# LED_Chaser.net
KiCad netlist of a schematic drawn in Altium Designer
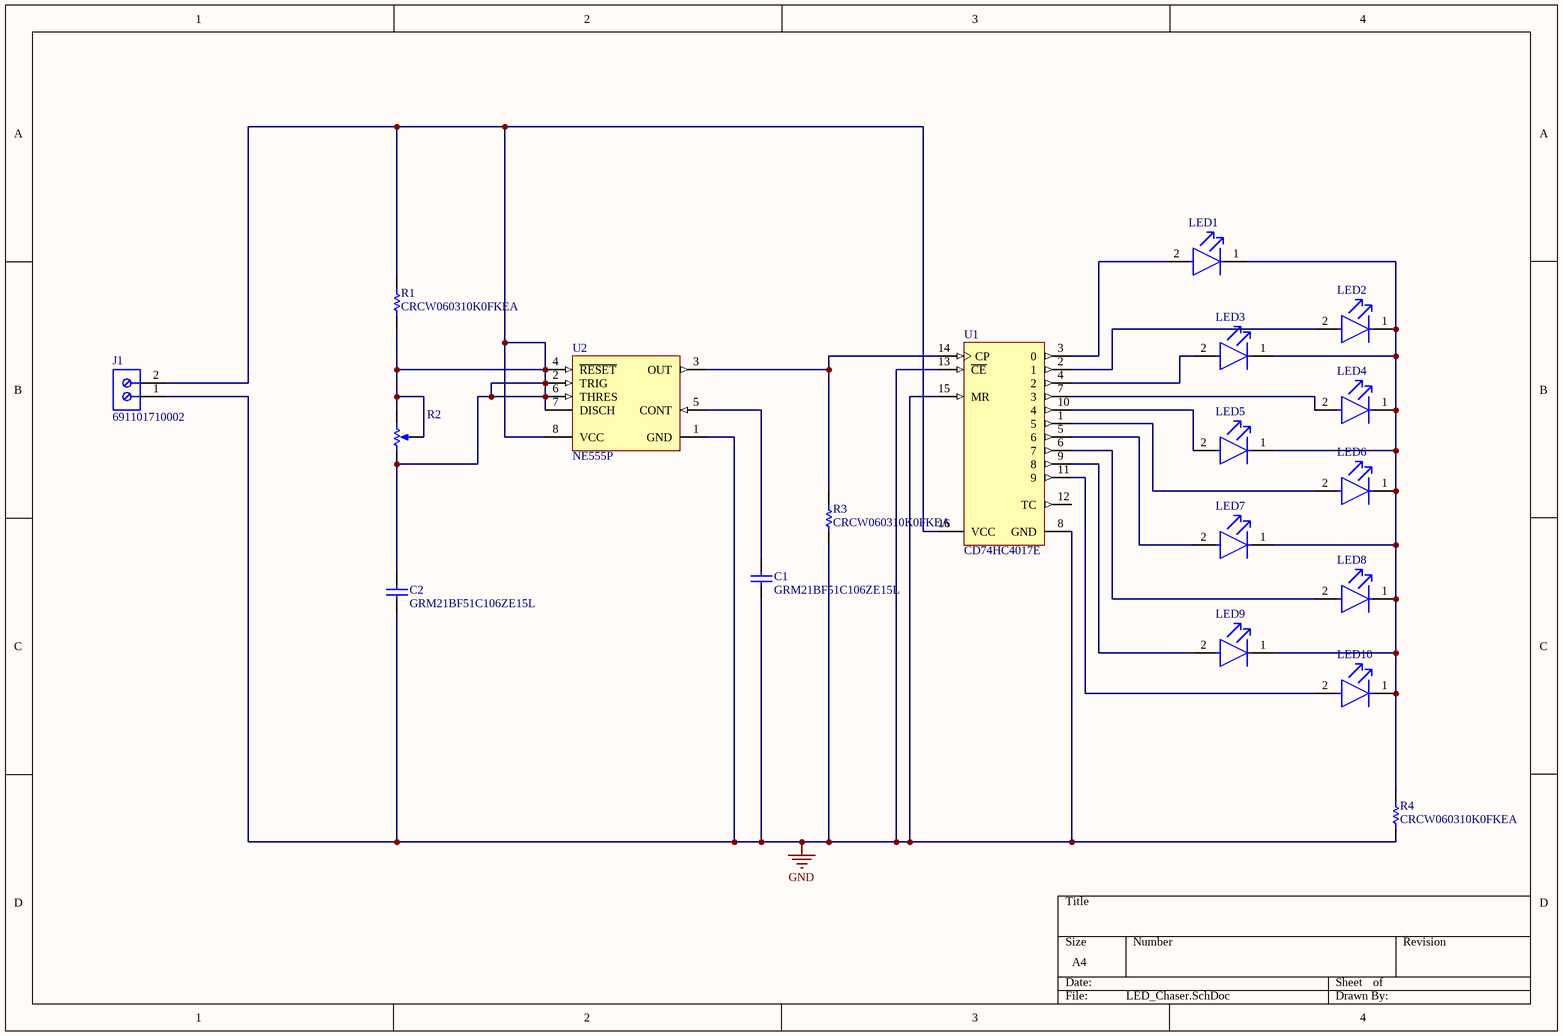
[diagram p0: LED_Chaser.SchDoc]

(export (version "E")
  (design (tool "Eeschema 10.0.6"))
  (components
    (comp (ref "C1")
      (value "GRM21BF51C106ZE15L")
      (footprint "CAPC2013X135X45NL10T25")
      (fields (field (name "MANUFACTURER") "Murata"))
      (libsource (lib "Altium Content Vault") (part "CAP"))
    )
    (comp (ref "C2")
      (value "GRM21BF51C106ZE15L")
      (footprint "CAPC2013X135X45NL10T25")
      (fields (field (name "MANUFACTURER") "Murata"))
      (libsource (lib "Altium Content Vault") (part "CAP"))
    )
    (comp (ref "J1")
      (value "691101710002")
      (footprint "691101710002")
      (fields (field (name "VOLTAGE") "250V"))
      (libsource (lib "Altium Content Vault") (part "TBL - 1R - 02P - Screw"))
    )
    (comp (ref "LED1")
      (value "~")
      (footprint "FP-LTST-C190GKT-MFG")
      (description "LED GREEN CLEAR CHIP SMD")
      (fields (field (name "VOLTAGE") "2V"))
      (libsource (lib "Altium Content Vault") (part "8706943c75ba83719d021d2fdc84c58"))
    )
    (comp (ref "LED2")
      (value "~")
      (footprint "FP-LTST-C190GKT-MFG")
      (description "LED GREEN CLEAR CHIP SMD")
      (fields (field (name "VOLTAGE") "2V"))
      (libsource (lib "Altium Content Vault") (part "8706943c75ba83719d021d2fdc84c58"))
    )
    (comp (ref "LED3")
      (value "~")
      (footprint "FP-LTST-C190GKT-MFG")
      (description "LED GREEN CLEAR CHIP SMD")
      (fields (field (name "VOLTAGE") "2V"))
      (libsource (lib "Altium Content Vault") (part "8706943c75ba83719d021d2fdc84c58"))
    )
    (comp (ref "LED4")
      (value "~")
      (footprint "FP-LTST-C190GKT-MFG")
      (description "LED GREEN CLEAR CHIP SMD")
      (fields (field (name "VOLTAGE") "2V"))
      (libsource (lib "Altium Content Vault") (part "8706943c75ba83719d021d2fdc84c58"))
    )
    (comp (ref "LED5")
      (value "~")
      (footprint "FP-LTST-C190GKT-MFG")
      (description "LED GREEN CLEAR CHIP SMD")
      (fields (field (name "VOLTAGE") "2V"))
      (libsource (lib "Altium Content Vault") (part "8706943c75ba83719d021d2fdc84c58"))
    )
    (comp (ref "LED6")
      (value "~")
      (footprint "FP-LTST-C190GKT-MFG")
      (description "LED GREEN CLEAR CHIP SMD")
      (fields (field (name "VOLTAGE") "2V"))
      (libsource (lib "Altium Content Vault") (part "8706943c75ba83719d021d2fdc84c58"))
    )
    (comp (ref "LED7")
      (value "~")
      (footprint "FP-LTST-C190GKT-MFG")
      (description "LED GREEN CLEAR CHIP SMD")
      (fields (field (name "VOLTAGE") "2V"))
      (libsource (lib "Altium Content Vault") (part "8706943c75ba83719d021d2fdc84c58"))
    )
    (comp (ref "LED8")
      (value "~")
      (footprint "FP-LTST-C190GKT-MFG")
      (description "LED GREEN CLEAR CHIP SMD")
      (fields (field (name "VOLTAGE") "2V"))
      (libsource (lib "Altium Content Vault") (part "8706943c75ba83719d021d2fdc84c58"))
    )
    (comp (ref "LED9")
      (value "~")
      (footprint "FP-LTST-C190GKT-MFG")
      (description "LED GREEN CLEAR CHIP SMD")
      (fields (field (name "VOLTAGE") "2V"))
      (libsource (lib "Altium Content Vault") (part "8706943c75ba83719d021d2fdc84c58"))
    )
    (comp (ref "LED10")
      (value "~")
      (footprint "FP-LTST-C190GKT-MFG")
      (description "LED GREEN CLEAR CHIP SMD")
      (fields (field (name "VOLTAGE") "2V"))
      (libsource (lib "Altium Content Vault") (part "8706943c75ba83719d021d2fdc84c58"))
    )
    (comp (ref "R1")
      (value "CRCW060310K0FKEA")
      (footprint "RESC1609X50X30NL8T20")
      (description "Chip Resistor, 10 KOhm, +/- 1%, 100 mW, -55 to 155 degC, 0603 (1608 Metric), RoHS, Tape and Reel")
      (fields (field (name "MANUFACTURER") "Vishay Semiconductor"))
      (libsource (lib "Altium Content Vault") (part "RES-2"))
    )
    (comp (ref "R2")
      (value "Potentiometer")
      (libsource (lib "Simulation Generic Components") (part "Potentiometer"))
    )
    (comp (ref "R3")
      (value "CRCW060310K0FKEA")
      (footprint "RESC1609X50X30NL8T20")
      (description "Chip Resistor, 10 KOhm, +/- 1%, 100 mW, -55 to 155 degC, 0603 (1608 Metric), RoHS, Tape and Reel")
      (fields (field (name "MANUFACTURER") "Vishay Semiconductor"))
      (libsource (lib "Altium Content Vault") (part "RES-2"))
    )
    (comp (ref "R4")
      (value "CRCW060310K0FKEA")
      (footprint "RESC1609X50X30NL8T20")
      (description "Chip Resistor, 10 KOhm, +/- 1%, 100 mW, -55 to 155 degC, 0603 (1608 Metric), RoHS, Tape and Reel")
      (fields (field (name "MANUFACTURER") "Vishay Semiconductor"))
      (libsource (lib "Altium Content Vault") (part "RES-2"))
    )
    (comp (ref "U1")
      (value "CD74HC4017E")
      (footprint "N0016A")
      (description "High Speed CMOS Logic Decade Counter/Divider with 10 Decoded Outputs, N0016A, TUBE")
      (fields
        (field (name "GENERIC PART NUMBER") "CD74HC4017")
        (field (name "MANUFACTURER") "Texas Instruments")
      )
      (libsource (lib "Altium Content Vault") (part "TI-CD74HC4017-16"))
    )
    (comp (ref "U2")
      (value "NE555P")
      (footprint "P0008A")
      (description "Precision Timer, 4.5 to 16 V, 0 to 70 degC, 8-Pin DIP, Pb-Free, Tube")
      (fields (field (name "MANUFACTURER") "TexasInstruments"))
      (libsource (lib "Altium Content Vault") (part "TI-NE555-P8"))
    )
  )
  (nets
    (net (code "1") (name "GND") (class "Default")
      (node (ref "C1") (pin "1") (pinfunction "1_1") (pintype "passive"))
      (node (ref "C2") (pin "1") (pinfunction "1_1") (pintype "passive"))
      (node (ref "J1") (pin "1") (pinfunction "1_1") (pintype "passive"))
      (node (ref "R3") (pin "1") (pinfunction "1_1") (pintype "passive"))
      (node (ref "R4") (pin "1") (pinfunction "1_1") (pintype "passive"))
      (node (ref "U1") (pin "13") (pinfunction "~{CE}_13") (pintype "input"))
      (node (ref "U1") (pin "15") (pinfunction "MR_15") (pintype "input"))
      (node (ref "U1") (pin "8") (pinfunction "GND_8") (pintype "power_in"))
      (node (ref "U2") (pin "1") (pinfunction "GND_1") (pintype "power_in"))
    )
    (net (code "2") (name "Net-(LED1-A)") (class "Default")
      (node (ref "LED1") (pin "2") (pinfunction "A_2") (pintype "passive"))
      (node (ref "U1") (pin "3") (pinfunction "0_3") (pintype "output"))
    )
    (net (code "3") (name "Net-(LED1-C)") (class "Default")
      (node (ref "LED1") (pin "1") (pinfunction "C_1") (pintype "passive"))
      (node (ref "LED10") (pin "1") (pinfunction "C_1") (pintype "passive"))
      (node (ref "LED2") (pin "1") (pinfunction "C_1") (pintype "passive"))
      (node (ref "LED3") (pin "1") (pinfunction "C_1") (pintype "passive"))
      (node (ref "LED4") (pin "1") (pinfunction "C_1") (pintype "passive"))
      (node (ref "LED5") (pin "1") (pinfunction "C_1") (pintype "passive"))
      (node (ref "LED6") (pin "1") (pinfunction "C_1") (pintype "passive"))
      (node (ref "LED7") (pin "1") (pinfunction "C_1") (pintype "passive"))
      (node (ref "LED8") (pin "1") (pinfunction "C_1") (pintype "passive"))
      (node (ref "LED9") (pin "1") (pinfunction "C_1") (pintype "passive"))
      (node (ref "R4") (pin "2") (pinfunction "2_2") (pintype "passive"))
    )
    (net (code "4") (name "Net-(LED2-A)") (class "Default")
      (node (ref "LED2") (pin "2") (pinfunction "A_2") (pintype "passive"))
      (node (ref "U1") (pin "2") (pinfunction "1_2") (pintype "output"))
    )
    (net (code "5") (name "Net-(LED3-A)") (class "Default")
      (node (ref "LED3") (pin "2") (pinfunction "A_2") (pintype "passive"))
      (node (ref "U1") (pin "4") (pinfunction "2_4") (pintype "output"))
    )
    (net (code "6") (name "Net-(LED4-A)") (class "Default")
      (node (ref "LED4") (pin "2") (pinfunction "A_2") (pintype "passive"))
      (node (ref "U1") (pin "7") (pinfunction "3_7") (pintype "output"))
    )
    (net (code "7") (name "Net-(LED5-A)") (class "Default")
      (node (ref "LED5") (pin "2") (pinfunction "A_2") (pintype "passive"))
      (node (ref "U1") (pin "10") (pinfunction "4_10") (pintype "output"))
    )
    (net (code "8") (name "Net-(LED6-A)") (class "Default")
      (node (ref "LED6") (pin "2") (pinfunction "A_2") (pintype "passive"))
      (node (ref "U1") (pin "1") (pinfunction "5_1") (pintype "output"))
    )
    (net (code "9") (name "Net-(LED7-A)") (class "Default")
      (node (ref "LED7") (pin "2") (pinfunction "A_2") (pintype "passive"))
      (node (ref "U1") (pin "5") (pinfunction "6_5") (pintype "output"))
    )
    (net (code "10") (name "Net-(LED8-A)") (class "Default")
      (node (ref "LED8") (pin "2") (pinfunction "A_2") (pintype "passive"))
      (node (ref "U1") (pin "6") (pinfunction "7_6") (pintype "output"))
    )
    (net (code "11") (name "Net-(LED9-A)") (class "Default")
      (node (ref "LED9") (pin "2") (pinfunction "A_2") (pintype "passive"))
      (node (ref "U1") (pin "9") (pinfunction "8_9") (pintype "output"))
    )
    (net (code "12") (name "Net-(LED10-A)") (class "Default")
      (node (ref "LED10") (pin "2") (pinfunction "A_2") (pintype "passive"))
      (node (ref "U1") (pin "11") (pinfunction "9_11") (pintype "output"))
    )
    (net (code "13") (name "Net-(R2-BOT)") (class "Default")
      (node (ref "C2") (pin "2") (pinfunction "2_2") (pintype "passive"))
      (node (ref "J1") (pin "2") (pinfunction "2_2") (pintype "passive"))
      (node (ref "R1") (pin "1") (pinfunction "1_1") (pintype "passive"))
      (node (ref "R1") (pin "2") (pinfunction "2_2") (pintype "passive"))
      (node (ref "R2") (pin "1") (pinfunction "TOP_1") (pintype "passive"))
      (node (ref "R2") (pin "2") (pinfunction "BOT_2") (pintype "passive"))
      (node (ref "R2") (pin "3") (pinfunction "TAP_3") (pintype "passive"))
      (node (ref "U1") (pin "16") (pinfunction "VCC_16") (pintype "power_in"))
      (node (ref "U2") (pin "2") (pinfunction "TRIG_2") (pintype "input"))
      (node (ref "U2") (pin "4") (pinfunction "~{RESET}_4") (pintype "input"))
      (node (ref "U2") (pin "6") (pinfunction "THRES_6") (pintype "input"))
      (node (ref "U2") (pin "7") (pinfunction "DISCH_7") (pintype "open_collector"))
      (node (ref "U2") (pin "8") (pinfunction "VCC_8") (pintype "power_in"))
    )
    (net (code "14") (name "Net-(U1-CP)") (class "Default")
      (node (ref "R3") (pin "2") (pinfunction "2_2") (pintype "passive"))
      (node (ref "U1") (pin "14") (pinfunction "CP_14") (pintype "input"))
      (node (ref "U2") (pin "3") (pinfunction "OUT_3") (pintype "output"))
    )
    (net (code "15") (name "Net-(U2-CONT)") (class "Default")
      (node (ref "C1") (pin "2") (pinfunction "2_2") (pintype "passive"))
      (node (ref "U2") (pin "5") (pinfunction "CONT_5") (pintype "input"))
    )
    (net (code "16") (name "unconnected-(U1-TC-Pad12)") (class "Default")
      (node (ref "U1") (pin "12") (pinfunction "TC_12") (pintype "output"))
    )
  )
)
